# heatersControl.net
KiCad netlist of a schematic drawn in Altium Designer
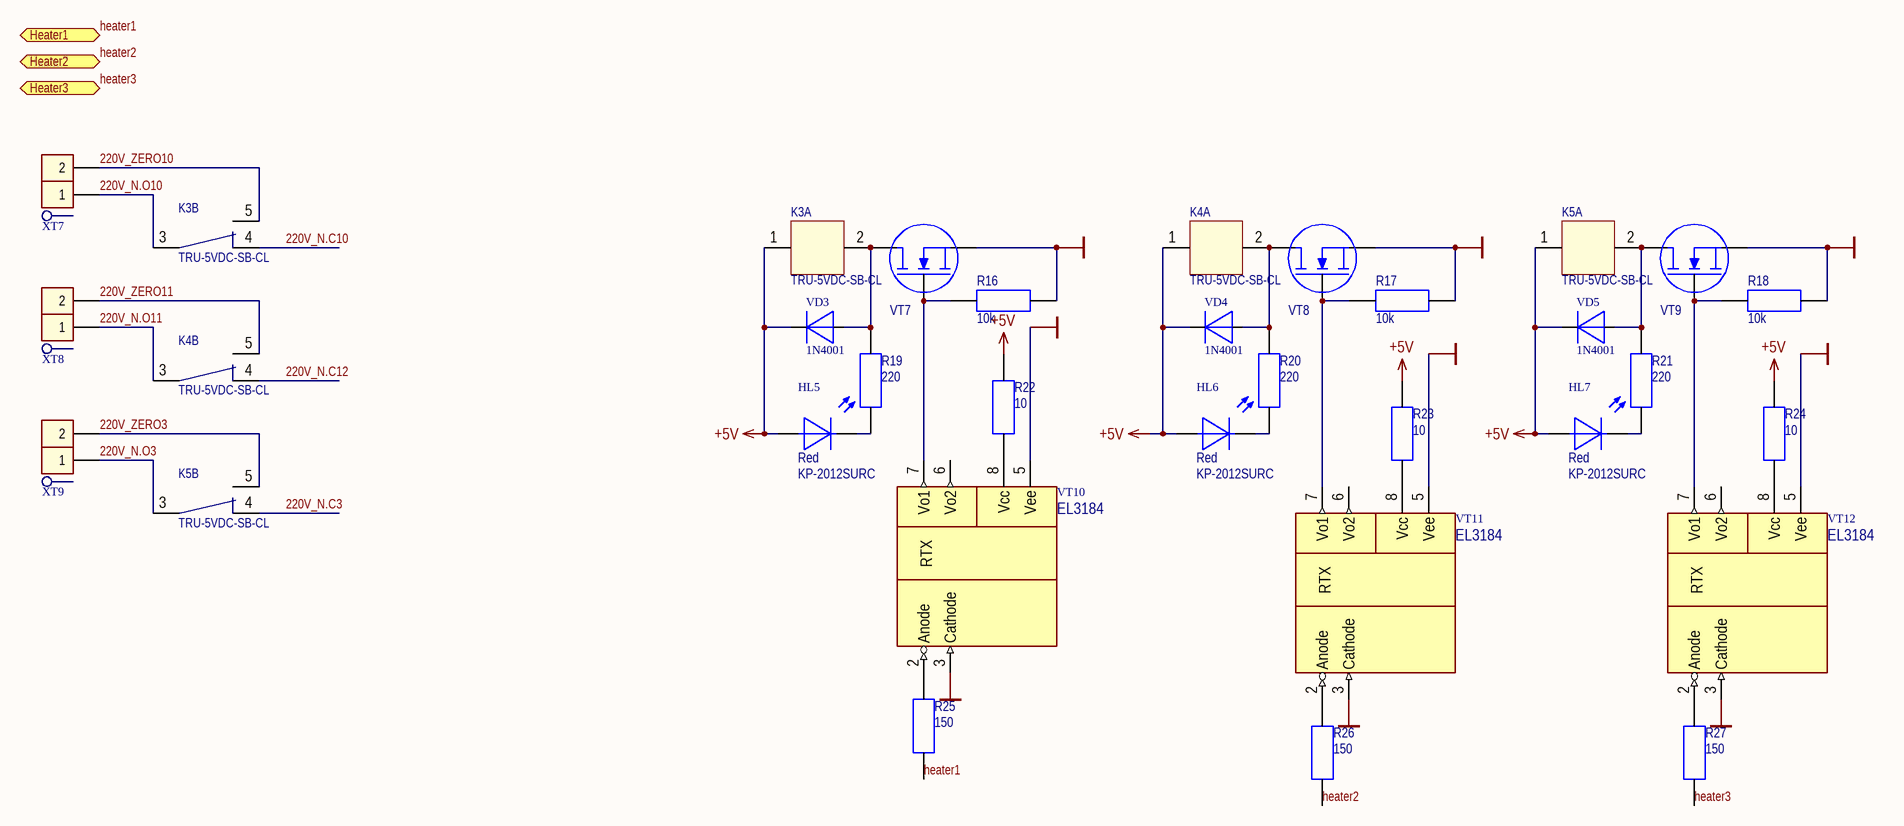
[diagram p0: heatersControl.SchDoc]

(export (version "E")
  (design (tool "Eeschema 10.0.6"))
  (components
    (comp (ref "HL5")
      (value "Red")
      (footprint "Indicator:DIOMELF2012M")
      (description "Diod LED SMD Red")
      (fields (field (name "MANUFACTURERPARTNUMBER") "KP-2012SURC"))
      (libsource (lib "Indicator") (part "LED1_R"))
    )
    (comp (ref "HL6")
      (value "Red")
      (footprint "Indicator:DIOMELF2012M")
      (description "Diod LED SMD Red")
      (fields (field (name "MANUFACTURERPARTNUMBER") "KP-2012SURC"))
      (libsource (lib "Indicator") (part "LED1_R"))
    )
    (comp (ref "HL7")
      (value "Red")
      (footprint "Indicator:DIOMELF2012M")
      (description "Diod LED SMD Red")
      (fields (field (name "MANUFACTURERPARTNUMBER") "KP-2012SURC"))
      (libsource (lib "Indicator") (part "LED1_R"))
    )
    (comp (ref "K3")
      (value "TRU-5VDC-SB-CL")
      (footprint "Switch:TRU-5VDC-SB-CL")
      (libsource (lib "Switch") (part "TRU-5VDC-SB-CL"))
    )
    (comp (ref "K4")
      (value "TRU-5VDC-SB-CL")
      (footprint "Switch:TRU-5VDC-SB-CL")
      (libsource (lib "Switch") (part "TRU-5VDC-SB-CL"))
    )
    (comp (ref "K5")
      (value "TRU-5VDC-SB-CL")
      (footprint "Switch:TRU-5VDC-SB-CL")
      (libsource (lib "Switch") (part "TRU-5VDC-SB-CL"))
    )
    (comp (ref "R16")
      (value "10k")
      (footprint "SMDRC0805")
      (description "Generic resistor")
      (fields (field (name "PARTNUMBER") "Resistor 0805 10k"))
      (libsource (lib "") (part "Resistor_1"))
    )
    (comp (ref "R17")
      (value "10k")
      (footprint "SMDRC0805")
      (description "Generic resistor")
      (fields (field (name "PARTNUMBER") "Resistor 0805 10k"))
      (libsource (lib "") (part "Resistor_1"))
    )
    (comp (ref "R18")
      (value "10k")
      (footprint "SMDRC0805")
      (description "Generic resistor")
      (fields (field (name "PARTNUMBER") "Resistor 0805 10k"))
      (libsource (lib "") (part "Resistor_1"))
    )
    (comp (ref "R19")
      (value "220")
      (footprint "SMDRC0805")
      (description "Generic resistor")
      (fields (field (name "PARTNUMBER") "Resistor 0805 220"))
      (libsource (lib "") (part "Resistor_2"))
    )
    (comp (ref "R20")
      (value "220")
      (footprint "SMDRC0805")
      (description "Generic resistor")
      (fields (field (name "PARTNUMBER") "Resistor 0805 220"))
      (libsource (lib "") (part "Resistor_2"))
    )
    (comp (ref "R21")
      (value "220")
      (footprint "SMDRC0805")
      (description "Generic resistor")
      (fields (field (name "PARTNUMBER") "Resistor 0805 220"))
      (libsource (lib "") (part "Resistor_2"))
    )
    (comp (ref "R22")
      (value "10")
      (footprint "SMDRC0805")
      (description "Generic resistor")
      (fields (field (name "PARTNUMBER") "Resistor 0805 10"))
      (libsource (lib "library") (part "Resistor"))
    )
    (comp (ref "R23")
      (value "10")
      (footprint "SMDRC0805")
      (description "Generic resistor")
      (fields (field (name "PARTNUMBER") "Resistor 0805 10"))
      (libsource (lib "library") (part "Resistor"))
    )
    (comp (ref "R24")
      (value "10")
      (footprint "SMDRC0805")
      (description "Generic resistor")
      (fields (field (name "PARTNUMBER") "Resistor 0805 10"))
      (libsource (lib "library") (part "Resistor"))
    )
    (comp (ref "R25")
      (value "150")
      (footprint "SMDRC0805")
      (description "Generic resistor")
      (fields (field (name "PARTNUMBER") "Resistor 0805 150"))
      (libsource (lib "library") (part "Resistor"))
    )
    (comp (ref "R26")
      (value "150")
      (footprint "SMDRC0805")
      (description "Generic resistor")
      (fields (field (name "PARTNUMBER") "Resistor 0805 150"))
      (libsource (lib "library") (part "Resistor"))
    )
    (comp (ref "R27")
      (value "150")
      (footprint "SMDRC0805")
      (description "Generic resistor")
      (fields (field (name "PARTNUMBER") "Resistor 0805 150"))
      (libsource (lib "library") (part "Resistor"))
    )
    (comp (ref "VD3")
      (value "1N4001")
      (footprint "DIod:PinDiode")
      (description "Rectifying diode")
      (fields (field (name "MANUFACTURERPARTNUMBER") "1N4001"))
      (libsource (lib "Diod") (part "1N4001"))
    )
    (comp (ref "VD4")
      (value "1N4001")
      (footprint "DIod:PinDiode")
      (description "Rectifying diode")
      (fields (field (name "MANUFACTURERPARTNUMBER") "1N4001"))
      (libsource (lib "Diod") (part "1N4001"))
    )
    (comp (ref "VD5")
      (value "1N4001")
      (footprint "DIod:PinDiode")
      (description "Rectifying diode")
      (fields (field (name "MANUFACTURERPARTNUMBER") "1N4001"))
      (libsource (lib "Diod") (part "1N4001"))
    )
    (comp (ref "VT7")
      (value "2N7002")
      (footprint "Standard:SOT23 (TO-236AB)")
      (description "60V, 300mA N-channel Trench MOSFET")
      (libsource (lib "Transistor") (part "2N7002 n-MOSFET"))
    )
    (comp (ref "VT8")
      (value "2N7002")
      (footprint "Standard:SOT23 (TO-236AB)")
      (description "60V, 300mA N-channel Trench MOSFET")
      (libsource (lib "Transistor") (part "2N7002 n-MOSFET"))
    )
    (comp (ref "VT9")
      (value "2N7002")
      (footprint "Standard:SOT23 (TO-236AB)")
      (description "60V, 300mA N-channel Trench MOSFET")
      (libsource (lib "Transistor") (part "2N7002 n-MOSFET"))
    )
    (comp (ref "VT10")
      (value "EL3184")
      (footprint "DIP8")
      (description "Optocouple IGBT driver")
      (fields
        (field (name "MANUFACTURER") "Everlight Electronics Co. Ltd")
        (field (name "MANUFACTURERPARTNUMBER") "EL3184")
      )
      (libsource (lib "Interface") (part "EL3184"))
    )
    (comp (ref "VT11")
      (value "EL3184")
      (footprint "DIP8")
      (description "Optocouple IGBT driver")
      (fields
        (field (name "MANUFACTURER") "Everlight Electronics Co. Ltd")
        (field (name "MANUFACTURERPARTNUMBER") "EL3184")
      )
      (libsource (lib "Interface") (part "EL3184"))
    )
    (comp (ref "VT12")
      (value "EL3184")
      (footprint "DIP8")
      (description "Optocouple IGBT driver")
      (fields
        (field (name "MANUFACTURER") "Everlight Electronics Co. Ltd")
        (field (name "MANUFACTURERPARTNUMBER") "EL3184")
      )
      (libsource (lib "Interface") (part "EL3184"))
    )
    (comp (ref "XT7")
      (value "305-021-12")
      (footprint "330-021-12")
      (description "Demountable connection  2-pin")
      (fields (field (name "MANUFACTURER") "Degson Electronics Co., Ltd"))
      (libsource (lib "Connector") (part "Con2_D 330-021-12"))
    )
    (comp (ref "XT8")
      (value "305-021-12")
      (footprint "330-021-12")
      (description "Demountable connection  2-pin")
      (fields (field (name "MANUFACTURER") "Degson Electronics Co., Ltd"))
      (libsource (lib "Connector") (part "Con2_D 330-021-12"))
    )
    (comp (ref "XT9")
      (value "305-021-12")
      (footprint "330-021-12")
      (description "Demountable connection  2-pin")
      (fields (field (name "MANUFACTURER") "Degson Electronics Co., Ltd"))
      (libsource (lib "Connector") (part "Con2_D 330-021-12"))
    )
  )
  (nets
    (net (code "1") (name "+5V") (class "Default")
      (node (ref "HL5") (pin "1") (pinfunction "1_1") (pintype "passive"))
      (node (ref "HL6") (pin "1") (pinfunction "1_1") (pintype "passive"))
      (node (ref "HL7") (pin "1") (pinfunction "1_1") (pintype "passive"))
      (node (ref "K3") (pin "1") (pinfunction "1_1") (pintype "passive"))
      (node (ref "K4") (pin "1") (pinfunction "1_1") (pintype "passive"))
      (node (ref "K5") (pin "1") (pinfunction "1_1") (pintype "passive"))
      (node (ref "R22") (pin "2") (pinfunction "2_2") (pintype "passive"))
      (node (ref "R23") (pin "2") (pinfunction "2_2") (pintype "passive"))
      (node (ref "R24") (pin "2") (pinfunction "2_2") (pintype "passive"))
      (node (ref "VD3") (pin "K") (pinfunction "K_K") (pintype "passive"))
      (node (ref "VD4") (pin "K") (pinfunction "K_K") (pintype "passive"))
      (node (ref "VD5") (pin "K") (pinfunction "K_K") (pintype "passive"))
    )
    (net (code "2") (name "/220V_N.C3") (class "Default")
      (node (ref "K5") (pin "4") (pinfunction "4_4") (pintype "passive"))
    )
    (net (code "3") (name "/220V_N.C10") (class "Default")
      (node (ref "K3") (pin "4") (pinfunction "4_4") (pintype "passive"))
    )
    (net (code "4") (name "/220V_N.C12") (class "Default")
      (node (ref "K4") (pin "4") (pinfunction "4_4") (pintype "passive"))
    )
    (net (code "5") (name "/220V_N.O3") (class "Default")
      (node (ref "K5") (pin "3") (pinfunction "3_3") (pintype "passive"))
      (node (ref "XT9") (pin "1") (pinfunction "1_1") (pintype "passive"))
    )
    (net (code "6") (name "/220V_N.O10") (class "Default")
      (node (ref "K3") (pin "3") (pinfunction "3_3") (pintype "passive"))
      (node (ref "XT7") (pin "1") (pinfunction "1_1") (pintype "passive"))
    )
    (net (code "7") (name "/220V_N.O11") (class "Default")
      (node (ref "K4") (pin "3") (pinfunction "3_3") (pintype "passive"))
      (node (ref "XT8") (pin "1") (pinfunction "1_1") (pintype "passive"))
    )
    (net (code "8") (name "/220V_ZERO3") (class "Default")
      (node (ref "K5") (pin "5") (pinfunction "5_5") (pintype "passive"))
      (node (ref "XT9") (pin "2") (pinfunction "2_2") (pintype "passive"))
    )
    (net (code "9") (name "/220V_ZERO10") (class "Default")
      (node (ref "K3") (pin "5") (pinfunction "5_5") (pintype "passive"))
      (node (ref "XT7") (pin "2") (pinfunction "2_2") (pintype "passive"))
    )
    (net (code "10") (name "/220V_ZERO11") (class "Default")
      (node (ref "K4") (pin "5") (pinfunction "5_5") (pintype "passive"))
      (node (ref "XT8") (pin "2") (pinfunction "2_2") (pintype "passive"))
    )
    (net (code "11") (name "/heater1") (class "Default")
      (node (ref "R25") (pin "1") (pinfunction "1_1") (pintype "passive"))
    )
    (net (code "12") (name "/heater2") (class "Default")
      (node (ref "R26") (pin "1") (pinfunction "1_1") (pintype "passive"))
    )
    (net (code "13") (name "/heater3") (class "Default")
      (node (ref "R27") (pin "1") (pinfunction "1_1") (pintype "passive"))
    )
    (net (code "14") (name "GND") (class "Default")
      (node (ref "R16") (pin "2") (pinfunction "2_2") (pintype "passive"))
      (node (ref "R17") (pin "2") (pinfunction "2_2") (pintype "passive"))
      (node (ref "R18") (pin "2") (pinfunction "2_2") (pintype "passive"))
      (node (ref "VT10") (pin "3") (pinfunction "Cathode_3") (pintype "input"))
      (node (ref "VT10") (pin "5") (pinfunction "Vee_5") (pintype "power_in"))
      (node (ref "VT11") (pin "3") (pinfunction "Cathode_3") (pintype "input"))
      (node (ref "VT11") (pin "5") (pinfunction "Vee_5") (pintype "power_in"))
      (node (ref "VT12") (pin "3") (pinfunction "Cathode_3") (pintype "input"))
      (node (ref "VT12") (pin "5") (pinfunction "Vee_5") (pintype "power_in"))
      (node (ref "VT7") (pin "2") (pinfunction "S_2") (pintype "passive"))
      (node (ref "VT8") (pin "2") (pinfunction "S_2") (pintype "passive"))
      (node (ref "VT9") (pin "2") (pinfunction "S_2") (pintype "passive"))
    )
    (net (code "15") (name "Net-(HL5-Pad2)") (class "Default")
      (node (ref "HL5") (pin "2") (pinfunction "2_2") (pintype "passive"))
      (node (ref "R19") (pin "2") (pinfunction "2_2") (pintype "passive"))
    )
    (net (code "16") (name "Net-(HL6-Pad2)") (class "Default")
      (node (ref "HL6") (pin "2") (pinfunction "2_2") (pintype "passive"))
      (node (ref "R20") (pin "2") (pinfunction "2_2") (pintype "passive"))
    )
    (net (code "17") (name "Net-(HL7-Pad2)") (class "Default")
      (node (ref "HL7") (pin "2") (pinfunction "2_2") (pintype "passive"))
      (node (ref "R21") (pin "2") (pinfunction "2_2") (pintype "passive"))
    )
    (net (code "18") (name "Net-(VT7-D)") (class "Default")
      (node (ref "K3") (pin "2") (pinfunction "2_2") (pintype "passive"))
      (node (ref "R19") (pin "1") (pinfunction "1_1") (pintype "passive"))
      (node (ref "VD3") (pin "A") (pinfunction "A_A") (pintype "passive"))
      (node (ref "VT7") (pin "3") (pinfunction "D_3") (pintype "passive"))
    )
    (net (code "19") (name "Net-(VT8-D)") (class "Default")
      (node (ref "K4") (pin "2") (pinfunction "2_2") (pintype "passive"))
      (node (ref "R20") (pin "1") (pinfunction "1_1") (pintype "passive"))
      (node (ref "VD4") (pin "A") (pinfunction "A_A") (pintype "passive"))
      (node (ref "VT8") (pin "3") (pinfunction "D_3") (pintype "passive"))
    )
    (net (code "20") (name "Net-(VT9-D)") (class "Default")
      (node (ref "K5") (pin "2") (pinfunction "2_2") (pintype "passive"))
      (node (ref "R21") (pin "1") (pinfunction "1_1") (pintype "passive"))
      (node (ref "VD5") (pin "A") (pinfunction "A_A") (pintype "passive"))
      (node (ref "VT9") (pin "3") (pinfunction "D_3") (pintype "passive"))
    )
    (net (code "21") (name "Net-(VT10-Anode)") (class "Default")
      (node (ref "R25") (pin "2") (pinfunction "2_2") (pintype "passive"))
      (node (ref "VT10") (pin "2") (pinfunction "Anode_2") (pintype "input"))
    )
    (net (code "22") (name "Net-(VT10-Vcc)") (class "Default")
      (node (ref "R22") (pin "1") (pinfunction "1_1") (pintype "passive"))
      (node (ref "VT10") (pin "8") (pinfunction "Vcc_8") (pintype "power_in"))
    )
    (net (code "23") (name "Net-(VT10-Vo1)") (class "Default")
      (node (ref "R16") (pin "1") (pinfunction "1_1") (pintype "passive"))
      (node (ref "VT10") (pin "7") (pinfunction "Vo1_7") (pintype "output"))
      (node (ref "VT7") (pin "1") (pinfunction "G_1") (pintype "passive"))
    )
    (net (code "24") (name "Net-(VT11-Anode)") (class "Default")
      (node (ref "R26") (pin "2") (pinfunction "2_2") (pintype "passive"))
      (node (ref "VT11") (pin "2") (pinfunction "Anode_2") (pintype "input"))
    )
    (net (code "25") (name "Net-(VT11-Vcc)") (class "Default")
      (node (ref "R23") (pin "1") (pinfunction "1_1") (pintype "passive"))
      (node (ref "VT11") (pin "8") (pinfunction "Vcc_8") (pintype "power_in"))
    )
    (net (code "26") (name "Net-(VT11-Vo1)") (class "Default")
      (node (ref "R17") (pin "1") (pinfunction "1_1") (pintype "passive"))
      (node (ref "VT11") (pin "7") (pinfunction "Vo1_7") (pintype "output"))
      (node (ref "VT8") (pin "1") (pinfunction "G_1") (pintype "passive"))
    )
    (net (code "27") (name "Net-(VT12-Anode)") (class "Default")
      (node (ref "R27") (pin "2") (pinfunction "2_2") (pintype "passive"))
      (node (ref "VT12") (pin "2") (pinfunction "Anode_2") (pintype "input"))
    )
    (net (code "28") (name "Net-(VT12-Vcc)") (class "Default")
      (node (ref "R24") (pin "1") (pinfunction "1_1") (pintype "passive"))
      (node (ref "VT12") (pin "8") (pinfunction "Vcc_8") (pintype "power_in"))
    )
    (net (code "29") (name "Net-(VT12-Vo1)") (class "Default")
      (node (ref "R18") (pin "1") (pinfunction "1_1") (pintype "passive"))
      (node (ref "VT12") (pin "7") (pinfunction "Vo1_7") (pintype "output"))
      (node (ref "VT9") (pin "1") (pinfunction "G_1") (pintype "passive"))
    )
    (net (code "30") (name "unconnected-(VT10-Vo2-Pad6)") (class "Default")
      (node (ref "VT10") (pin "6") (pinfunction "Vo2_6") (pintype "output"))
    )
    (net (code "31") (name "unconnected-(VT11-Vo2-Pad6)") (class "Default")
      (node (ref "VT11") (pin "6") (pinfunction "Vo2_6") (pintype "output"))
    )
    (net (code "32") (name "unconnected-(VT12-Vo2-Pad6)") (class "Default")
      (node (ref "VT12") (pin "6") (pinfunction "Vo2_6") (pintype "output"))
    )
  )
)
